# EDU_High-Speed-Design_CPU_LVDS.net
KiCad netlist of a schematic drawn in Altium Designer
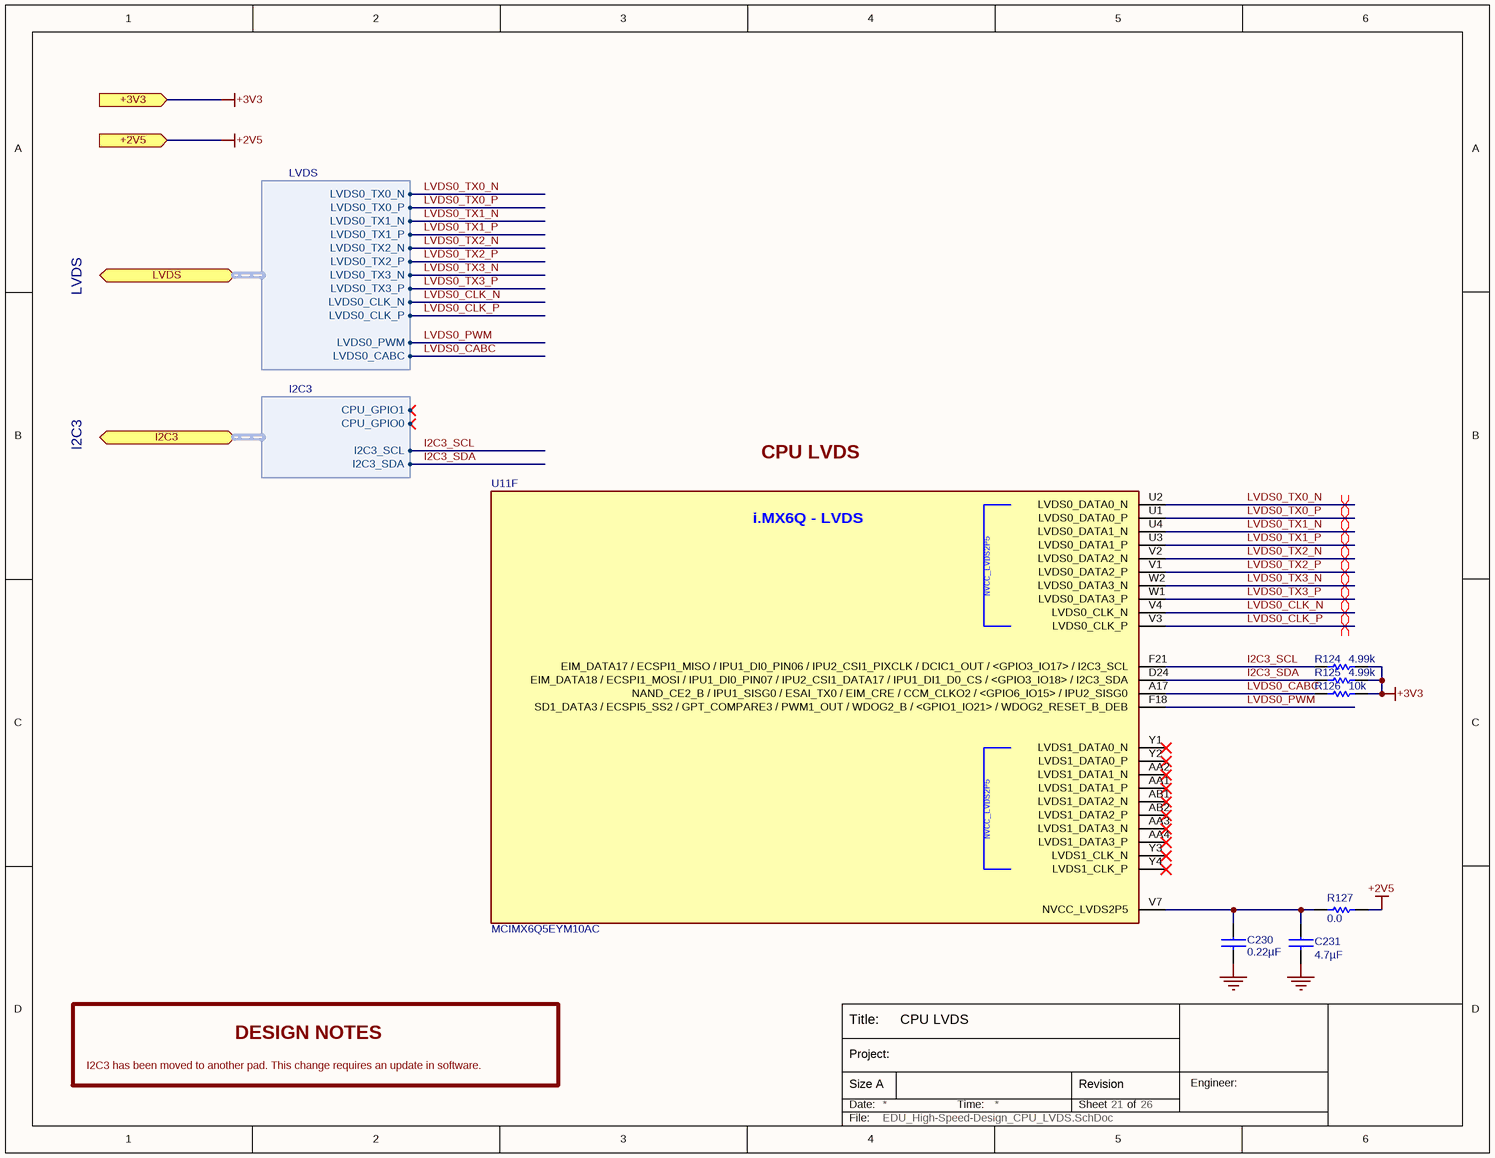
[diagram p0: EDU_High-Speed-Design_CPU_LVDS.SchDoc]

(export (version "E")
  (design (tool "Eeschema 10.0.6"))
  (components
    (comp (ref "C230")
      (value "0.22µF")
      (footprint "C0402")
      (description "CAP CER .22UF 25V X5R 20% 0402")
      (fields (field (name "VOLTAGE") "25V"))
      (libsource (lib "EDU_High-Speed-Design") (part "C1005X5R1E224M"))
    )
    (comp (ref "C231")
      (value "4.7µF")
      (footprint "C0402")
      (description "CAP CER 4.7UF 10V 20% X5R 0402")
      (fields (field (name "VOLTAGE") "10V"))
      (libsource (lib "EDU_High-Speed-Design") (part "C1005X5R1A475M"))
    )
    (comp (ref "R124")
      (value "4.99k")
      (footprint "R0402")
      (description "RES TF 4.99K OHM 1% 1/16W 0402")
      (libsource (lib "EDU_High-Speed-Design") (part "RMCF0402FT4K99"))
    )
    (comp (ref "R125")
      (value "4.99k")
      (footprint "R0402")
      (description "RES TF 4.99K OHM 1% 1/16W 0402")
      (libsource (lib "EDU_High-Speed-Design") (part "RMCF0402FT4K99"))
    )
    (comp (ref "R126")
      (value "10k")
      (footprint "R0402")
      (description "RES 10.0K OHM 1/16W 1% 0402 SMD")
      (libsource (lib "EDU_High-Speed-Design") (part "RC0402FR-0710KL"))
    )
    (comp (ref "R127")
      (value "0.0")
      (footprint "R0402")
      (description "RES 0.0 OHM 1/16W 0402 SMD")
      (libsource (lib "EDU_High-Speed-Design") (part "RC0402JR-070RL"))
    )
    (comp (ref "U11")
      (value "MCIMX6Q5EYM10AC")
      (footprint "MCIMX6Q5EYM10AC")
      (description "IC MCU 32BIT ARM QUAD 624FCBGA")
      (libsource (lib "EDU_High-Speed-Design") (part "MCIMX6Q5EYM10AC"))
    )
  )
  (nets
    (net (code "3") (name "+2V5") (class "Default")
      (node (ref "R127") (pin "2") (pinfunction "2_2") (pintype "passive"))
    )
    (net (code "4") (name "+3V3") (class "Default")
      (node (ref "R124") (pin "1") (pinfunction "1_1") (pintype "passive"))
      (node (ref "R125") (pin "1") (pinfunction "1_1") (pintype "passive"))
      (node (ref "R126") (pin "2") (pinfunction "2_2") (pintype "passive"))
    )
    (net (code "5") (name "/I2C3_SCL") (class "Default")
      (node (ref "R124") (pin "2") (pinfunction "2_2") (pintype "passive"))
      (node (ref "U11") (pin "F21") (pinfunction "EIM_DATA17_/_ECSPI1_MISO_/_IPU1_DI0_PIN06_/_IPU2_CSI1_PIXCLK_/_DCIC1_OUT_/_<GPIO3_IO17>_/_I2C3_SCL_F21") (pintype "passive"))
    )
    (net (code "6") (name "/I2C3_SDA") (class "Default")
      (node (ref "R125") (pin "2") (pinfunction "2_2") (pintype "passive"))
      (node (ref "U11") (pin "D24") (pinfunction "EIM_DATA18_/_ECSPI1_MOSI_/_IPU1_DI0_PIN07_/_IPU2_CSI1_DATA17_/_IPU1_DI1_D0_CS_/_<GPIO3_IO18>_/_I2C3_SDA_D24") (pintype "passive"))
    )
    (net (code "7") (name "/LVDS0_CABC") (class "Default")
      (node (ref "R126") (pin "1") (pinfunction "1_1") (pintype "passive"))
      (node (ref "U11") (pin "A17") (pinfunction "NAND_CE2_B_/_IPU1_SISG0_/_ESAI_TX0_/_EIM_CRE_/_CCM_CLKO2_/_<GPIO6_IO15>_/_IPU2_SISG0_A17") (pintype "passive"))
    )
    (net (code "8") (name "/LVDS0_CLK_N") (class "Default")
      (node (ref "U11") (pin "V4") (pinfunction "LVDS0_CLK_N_V4") (pintype "passive"))
    )
    (net (code "9") (name "/LVDS0_CLK_P") (class "Default")
      (node (ref "U11") (pin "V3") (pinfunction "LVDS0_CLK_P_V3") (pintype "passive"))
    )
    (net (code "10") (name "/LVDS0_PWM") (class "Default")
      (node (ref "U11") (pin "F18") (pinfunction "SD1_DATA3_/_ECSPI5_SS2_/_GPT_COMPARE3_/_PWM1_OUT_/_WDOG2_B_/_<GPIO1_IO21>_/_WDOG2_RESET_B_DEB_F18") (pintype "passive"))
    )
    (net (code "11") (name "/LVDS0_TX0_N") (class "Default")
      (node (ref "U11") (pin "U2") (pinfunction "LVDS0_DATA0_N_U2") (pintype "passive"))
    )
    (net (code "12") (name "/LVDS0_TX0_P") (class "Default")
      (node (ref "U11") (pin "U1") (pinfunction "LVDS0_DATA0_P_U1") (pintype "passive"))
    )
    (net (code "13") (name "/LVDS0_TX1_N") (class "Default")
      (node (ref "U11") (pin "U4") (pinfunction "LVDS0_DATA1_N_U4") (pintype "passive"))
    )
    (net (code "14") (name "/LVDS0_TX1_P") (class "Default")
      (node (ref "U11") (pin "U3") (pinfunction "LVDS0_DATA1_P_U3") (pintype "passive"))
    )
    (net (code "15") (name "/LVDS0_TX2_N") (class "Default")
      (node (ref "U11") (pin "V2") (pinfunction "LVDS0_DATA2_N_V2") (pintype "passive"))
    )
    (net (code "16") (name "/LVDS0_TX2_P") (class "Default")
      (node (ref "U11") (pin "V1") (pinfunction "LVDS0_DATA2_P_V1") (pintype "passive"))
    )
    (net (code "17") (name "/LVDS0_TX3_N") (class "Default")
      (node (ref "U11") (pin "W2") (pinfunction "LVDS0_DATA3_N_W2") (pintype "passive"))
    )
    (net (code "18") (name "/LVDS0_TX3_P") (class "Default")
      (node (ref "U11") (pin "W1") (pinfunction "LVDS0_DATA3_P_W1") (pintype "passive"))
    )
    (net (code "21") (name "GND") (class "Default")
      (node (ref "C230") (pin "2") (pinfunction "2_2") (pintype "passive"))
      (node (ref "C231") (pin "2") (pinfunction "2_2") (pintype "passive"))
    )
    (net (code "22") (name "Net-(U11F-NVCC_LVDS2P5)") (class "Default")
      (node (ref "C230") (pin "1") (pinfunction "1_1") (pintype "passive"))
      (node (ref "C231") (pin "1") (pinfunction "1_1") (pintype "passive"))
      (node (ref "R127") (pin "1") (pinfunction "1_1") (pintype "passive"))
      (node (ref "U11") (pin "V7") (pinfunction "NVCC_LVDS2P5_V7") (pintype "passive"))
    )
    (net (code "23") (name "unconnected-(U11F-LVDS1_CLK_N-PadY3)") (class "Default")
      (node (ref "U11") (pin "Y3") (pinfunction "LVDS1_CLK_N_Y3") (pintype "passive+no_connect"))
    )
    (net (code "24") (name "unconnected-(U11F-LVDS1_CLK_P-PadY4)") (class "Default")
      (node (ref "U11") (pin "Y4") (pinfunction "LVDS1_CLK_P_Y4") (pintype "passive+no_connect"))
    )
    (net (code "25") (name "unconnected-(U11F-LVDS1_DATA0_N-PadY1)") (class "Default")
      (node (ref "U11") (pin "Y1") (pinfunction "LVDS1_DATA0_N_Y1") (pintype "passive+no_connect"))
    )
    (net (code "26") (name "unconnected-(U11F-LVDS1_DATA0_P-PadY2)") (class "Default")
      (node (ref "U11") (pin "Y2") (pinfunction "LVDS1_DATA0_P_Y2") (pintype "passive+no_connect"))
    )
    (net (code "27") (name "unconnected-(U11F-LVDS1_DATA1_N-PadAA2)") (class "Default")
      (node (ref "U11") (pin "AA2") (pinfunction "LVDS1_DATA1_N_AA2") (pintype "passive+no_connect"))
    )
    (net (code "28") (name "unconnected-(U11F-LVDS1_DATA1_P-PadAA1)") (class "Default")
      (node (ref "U11") (pin "AA1") (pinfunction "LVDS1_DATA1_P_AA1") (pintype "passive+no_connect"))
    )
    (net (code "29") (name "unconnected-(U11F-LVDS1_DATA2_N-PadAB1)") (class "Default")
      (node (ref "U11") (pin "AB1") (pinfunction "LVDS1_DATA2_N_AB1") (pintype "passive+no_connect"))
    )
    (net (code "30") (name "unconnected-(U11F-LVDS1_DATA2_P-PadAB2)") (class "Default")
      (node (ref "U11") (pin "AB2") (pinfunction "LVDS1_DATA2_P_AB2") (pintype "passive+no_connect"))
    )
    (net (code "31") (name "unconnected-(U11F-LVDS1_DATA3_N-PadAA3)") (class "Default")
      (node (ref "U11") (pin "AA3") (pinfunction "LVDS1_DATA3_N_AA3") (pintype "passive+no_connect"))
    )
    (net (code "32") (name "unconnected-(U11F-LVDS1_DATA3_P-PadAA4)") (class "Default")
      (node (ref "U11") (pin "AA4") (pinfunction "LVDS1_DATA3_P_AA4") (pintype "passive+no_connect"))
    )
  )
)
